# Part_L.net
KiCad netlist of a schematic drawn in Altium Designer
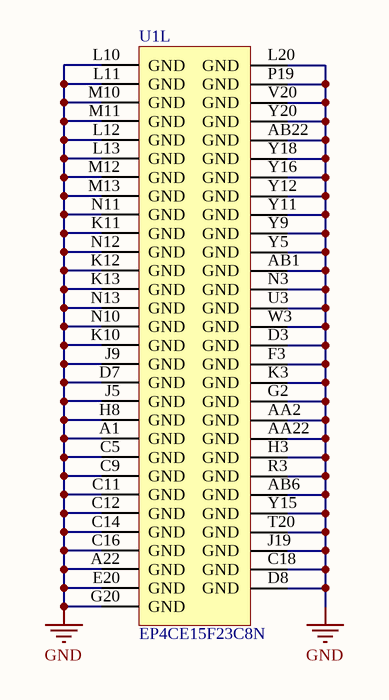
[diagram p0: Part L.SchDoc]

(export (version "E")
  (design (tool "Eeschema 10.0.6"))
  (components
    (comp (ref "U1")
      (value "EP4CE15F23C8N")
      (footprint "FBGA484_A-240")
      (fields (field (name "MANUFACTURER") "Altera"))
      (libsource (lib "Schlib1") (part "FPGA_EP4CE15F23C8N"))
    )
  )
  (nets
    (net (code "1") (name "GND") (class "Default")
      (node (ref "U1") (pin "A1") (pinfunction "GND_A1") (pintype "power_in"))
      (node (ref "U1") (pin "A22") (pinfunction "GND_A22") (pintype "power_in"))
      (node (ref "U1") (pin "AA2") (pinfunction "GND_AA2") (pintype "power_in"))
      (node (ref "U1") (pin "AA22") (pinfunction "GND_AA22") (pintype "power_in"))
      (node (ref "U1") (pin "AB1") (pinfunction "GND_AB1") (pintype "power_in"))
      (node (ref "U1") (pin "AB22") (pinfunction "GND_AB22") (pintype "power_in"))
      (node (ref "U1") (pin "AB6") (pinfunction "GND_AB6") (pintype "power_in"))
      (node (ref "U1") (pin "C11") (pinfunction "GND_C11") (pintype "power_in"))
      (node (ref "U1") (pin "C12") (pinfunction "GND_C12") (pintype "power_in"))
      (node (ref "U1") (pin "C14") (pinfunction "GND_C14") (pintype "power_in"))
      (node (ref "U1") (pin "C16") (pinfunction "GND_C16") (pintype "power_in"))
      (node (ref "U1") (pin "C18") (pinfunction "GND_C18") (pintype "power_in"))
      (node (ref "U1") (pin "C5") (pinfunction "GND_C5") (pintype "power_in"))
      (node (ref "U1") (pin "C9") (pinfunction "GND_C9") (pintype "power_in"))
      (node (ref "U1") (pin "D3") (pinfunction "GND_D3") (pintype "power_in"))
      (node (ref "U1") (pin "D7") (pinfunction "GND_D7") (pintype "power_in"))
      (node (ref "U1") (pin "D8") (pinfunction "GND_D8") (pintype "power_in"))
      (node (ref "U1") (pin "E20") (pinfunction "GND_E20") (pintype "power_in"))
      (node (ref "U1") (pin "F3") (pinfunction "GND_F3") (pintype "power_in"))
      (node (ref "U1") (pin "G2") (pinfunction "GND_G2") (pintype "power_in"))
      (node (ref "U1") (pin "G20") (pinfunction "GND_G20") (pintype "power_in"))
      (node (ref "U1") (pin "H3") (pinfunction "GND_H3") (pintype "power_in"))
      (node (ref "U1") (pin "H8") (pinfunction "GND_H8") (pintype "power_in"))
      (node (ref "U1") (pin "J19") (pinfunction "GND_J19") (pintype "power_in"))
      (node (ref "U1") (pin "J5") (pinfunction "GND_J5") (pintype "power_in"))
      (node (ref "U1") (pin "J9") (pinfunction "GND_J9") (pintype "power_in"))
      (node (ref "U1") (pin "K10") (pinfunction "GND_K10") (pintype "power_in"))
      (node (ref "U1") (pin "K11") (pinfunction "GND_K11") (pintype "power_in"))
      (node (ref "U1") (pin "K12") (pinfunction "GND_K12") (pintype "power_in"))
      (node (ref "U1") (pin "K13") (pinfunction "GND_K13") (pintype "power_in"))
      (node (ref "U1") (pin "K3") (pinfunction "GND_K3") (pintype "power_in"))
      (node (ref "U1") (pin "L10") (pinfunction "GND_L10") (pintype "power_in"))
      (node (ref "U1") (pin "L11") (pinfunction "GND_L11") (pintype "power_in"))
      (node (ref "U1") (pin "L12") (pinfunction "GND_L12") (pintype "power_in"))
      (node (ref "U1") (pin "L13") (pinfunction "GND_L13") (pintype "power_in"))
      (node (ref "U1") (pin "L20") (pinfunction "GND_L20") (pintype "power_in"))
      (node (ref "U1") (pin "M10") (pinfunction "GND_M10") (pintype "power_in"))
      (node (ref "U1") (pin "M11") (pinfunction "GND_M11") (pintype "power_in"))
      (node (ref "U1") (pin "M12") (pinfunction "GND_M12") (pintype "power_in"))
      (node (ref "U1") (pin "M13") (pinfunction "GND_M13") (pintype "power_in"))
      (node (ref "U1") (pin "N10") (pinfunction "GND_N10") (pintype "power_in"))
      (node (ref "U1") (pin "N11") (pinfunction "GND_N11") (pintype "power_in"))
      (node (ref "U1") (pin "N12") (pinfunction "GND_N12") (pintype "power_in"))
      (node (ref "U1") (pin "N13") (pinfunction "GND_N13") (pintype "power_in"))
      (node (ref "U1") (pin "N3") (pinfunction "GND_N3") (pintype "power_in"))
      (node (ref "U1") (pin "P19") (pinfunction "GND_P19") (pintype "power_in"))
      (node (ref "U1") (pin "R3") (pinfunction "GND_R3") (pintype "power_in"))
      (node (ref "U1") (pin "T20") (pinfunction "GND_T20") (pintype "power_in"))
      (node (ref "U1") (pin "U3") (pinfunction "GND_U3") (pintype "power_in"))
      (node (ref "U1") (pin "V20") (pinfunction "GND_V20") (pintype "power_in"))
      (node (ref "U1") (pin "W3") (pinfunction "GND_W3") (pintype "power_in"))
      (node (ref "U1") (pin "Y11") (pinfunction "GND_Y11") (pintype "power_in"))
      (node (ref "U1") (pin "Y12") (pinfunction "GND_Y12") (pintype "power_in"))
      (node (ref "U1") (pin "Y15") (pinfunction "GND_Y15") (pintype "power_in"))
      (node (ref "U1") (pin "Y16") (pinfunction "GND_Y16") (pintype "power_in"))
      (node (ref "U1") (pin "Y18") (pinfunction "GND_Y18") (pintype "power_in"))
      (node (ref "U1") (pin "Y20") (pinfunction "GND_Y20") (pintype "power_in"))
      (node (ref "U1") (pin "Y5") (pinfunction "GND_Y5") (pintype "power_in"))
      (node (ref "U1") (pin "Y9") (pinfunction "GND_Y9") (pintype "power_in"))
    )
  )
)
